# HID.net
KiCad netlist of a schematic drawn in Altium Designer
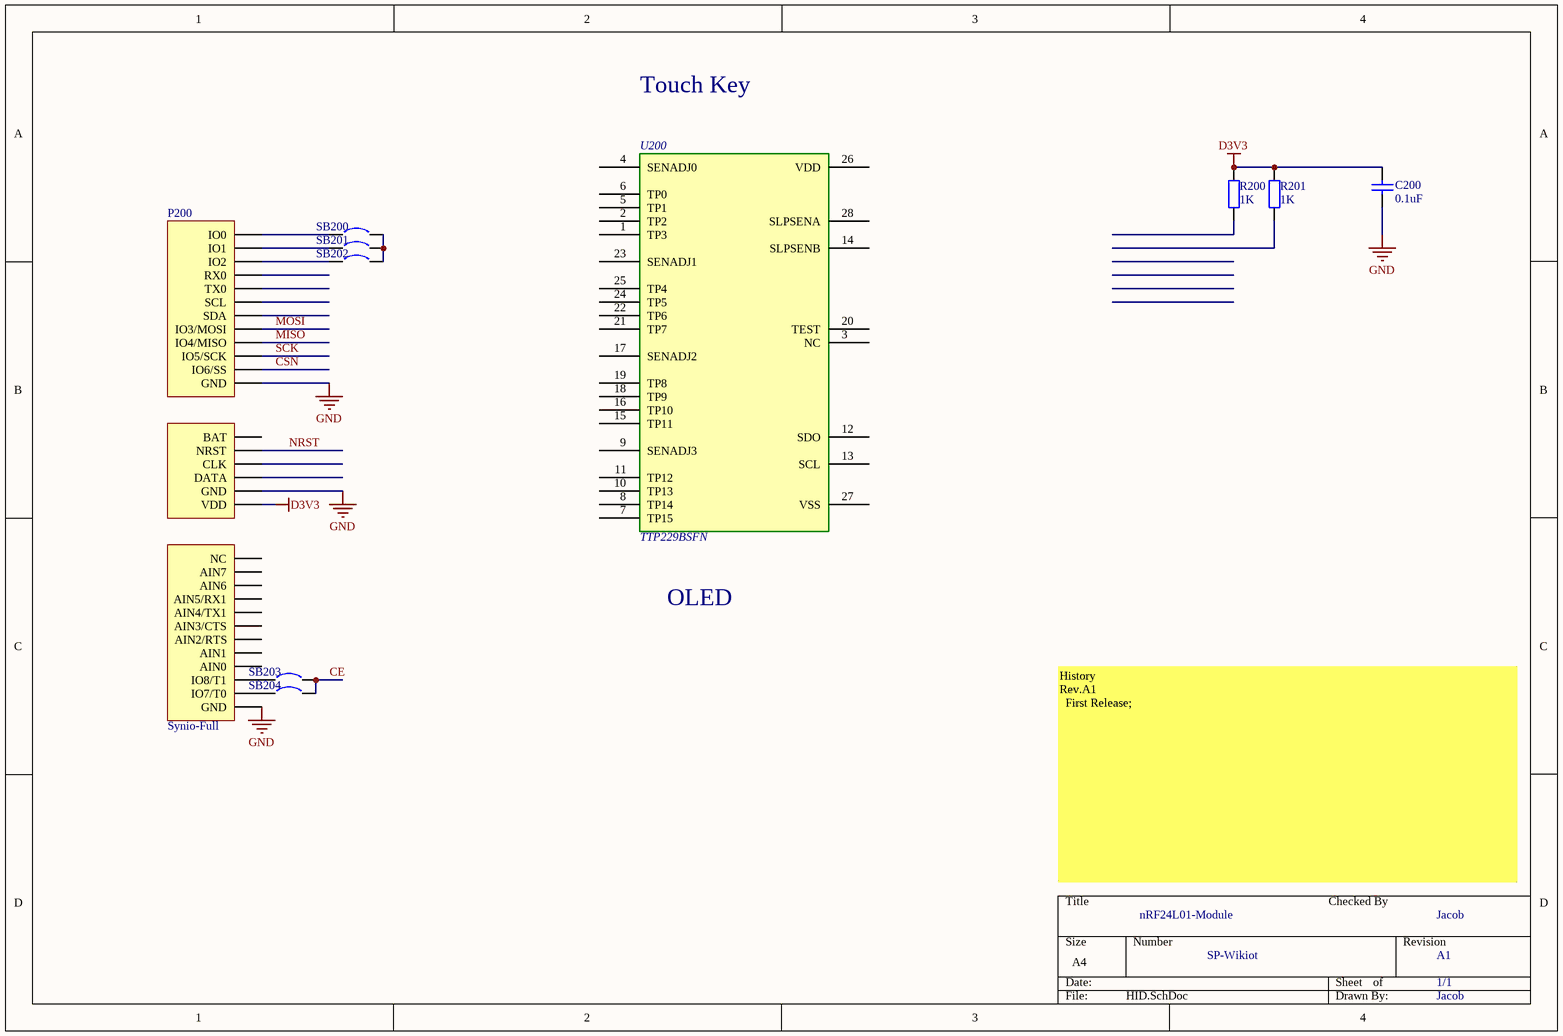
[diagram p0: HID.SchDoc]

(export (version "E")
  (design (tool "Eeschema 10.0.6"))
  (components
    (comp (ref "C200")
      (value "0.1uF")
      (footprint "C0603L")
      (description "Capacitor")
      (libsource (lib "Misc") (part "Cap"))
    )
    (comp (ref "P200")
      (value "Synio-Full")
      (footprint "Synio-Full")
      (description "Synio-Full Header")
      (libsource (lib "Connector") (part "Synio-Full"))
    )
    (comp (ref "R200")
      (value "1K")
      (footprint "R0603")
      (description "Resistor")
      (fields (field (name "PUBLISHER") "Altium Limited"))
      (libsource (lib "Misc") (part "Res"))
    )
    (comp (ref "R201")
      (value "1K")
      (footprint "R0603")
      (description "Resistor")
      (fields (field (name "PUBLISHER") "Altium Limited"))
      (libsource (lib "Misc") (part "Res"))
    )
    (comp (ref "SB200")
      (value "Circuit Breaker")
      (footprint "JP2_SMD")
      (fields (field (name "PUBLISHER") "Altium Limited"))
      (libsource (lib "Misc") (part "Circuit Breaker"))
    )
    (comp (ref "SB201")
      (value "Circuit Breaker")
      (footprint "JP2_SMD")
      (fields (field (name "PUBLISHER") "Altium Limited"))
      (libsource (lib "Misc") (part "Circuit Breaker"))
    )
    (comp (ref "SB202")
      (value "Circuit Breaker")
      (footprint "JP2_SMD")
      (fields (field (name "PUBLISHER") "Altium Limited"))
      (libsource (lib "Misc") (part "Circuit Breaker"))
    )
    (comp (ref "SB203")
      (value "Circuit Breaker")
      (footprint "JP2_SMD")
      (fields (field (name "PUBLISHER") "Altium Limited"))
      (libsource (lib "Misc") (part "Circuit Breaker"))
    )
    (comp (ref "SB204")
      (value "Circuit Breaker")
      (footprint "JP2_SMD")
      (fields (field (name "PUBLISHER") "Altium Limited"))
      (libsource (lib "Misc") (part "Circuit Breaker"))
    )
    (comp (ref "U200")
      (value "TTP229BSFN")
      (footprint "TSSOP28")
      (description "TOUCH PAD DETECTOR IC")
      (libsource (lib "Logic") (part "TP229BSFN"))
    )
  )
  (nets
    (net (code "1") (name "/CE") (class "Default")
      (node (ref "SB203") (pin "2") (pinfunction "2_2") (pintype "passive"))
      (node (ref "SB204") (pin "2") (pinfunction "2_2") (pintype "passive"))
    )
    (net (code "2") (name "/CSN") (class "Default")
      (node (ref "P200") (pin "11") (pinfunction "IO6/SS_11") (pintype "passive"))
    )
    (net (code "3") (name "/MISO") (class "Default")
      (node (ref "P200") (pin "9") (pinfunction "IO4/MISO_9") (pintype "passive"))
    )
    (net (code "4") (name "/MOSI") (class "Default")
      (node (ref "P200") (pin "8") (pinfunction "IO3/MOSI_8") (pintype "passive"))
    )
    (net (code "5") (name "/NRST") (class "Default")
      (node (ref "P200") (pin "14") (pinfunction "NRST_14") (pintype "passive"))
    )
    (net (code "6") (name "/SCK") (class "Default")
      (node (ref "P200") (pin "10") (pinfunction "IO5/SCK_10") (pintype "passive"))
    )
    (net (code "7") (name "D3V3") (class "Default")
      (node (ref "C200") (pin "1") (pinfunction "1_1") (pintype "passive"))
      (node (ref "P200") (pin "18") (pinfunction "VDD_18") (pintype "passive"))
      (node (ref "R200") (pin "1") (pinfunction "1_1") (pintype "passive"))
      (node (ref "R201") (pin "1") (pinfunction "1_1") (pintype "passive"))
    )
    (net (code "8") (name "GND") (class "Default")
      (node (ref "C200") (pin "2") (pinfunction "2_2") (pintype "passive"))
      (node (ref "P200") (pin "12") (pinfunction "GND_12") (pintype "passive"))
      (node (ref "P200") (pin "17") (pinfunction "GND_17") (pintype "passive"))
      (node (ref "P200") (pin "19") (pinfunction "GND_19") (pintype "passive"))
    )
    (net (code "9") (name "Net-(P200-IO0)") (class "Default")
      (node (ref "P200") (pin "1") (pinfunction "IO0_1") (pintype "passive"))
      (node (ref "SB200") (pin "1") (pinfunction "1_1") (pintype "passive"))
    )
    (net (code "10") (name "Net-(P200-IO1)") (class "Default")
      (node (ref "P200") (pin "2") (pinfunction "IO1_2") (pintype "passive"))
      (node (ref "SB201") (pin "1") (pinfunction "1_1") (pintype "passive"))
    )
    (net (code "11") (name "Net-(P200-IO2)") (class "Default")
      (node (ref "P200") (pin "3") (pinfunction "IO2_3") (pintype "passive"))
      (node (ref "SB202") (pin "1") (pinfunction "1_1") (pintype "passive"))
    )
    (net (code "12") (name "Net-(P200-IO7{slash}T0)") (class "Default")
      (node (ref "P200") (pin "20") (pinfunction "IO7/T0_20") (pintype "passive"))
      (node (ref "SB204") (pin "1") (pinfunction "1_1") (pintype "passive"))
    )
    (net (code "13") (name "Net-(P200-IO8{slash}T1)") (class "Default")
      (node (ref "P200") (pin "21") (pinfunction "IO8/T1_21") (pintype "passive"))
      (node (ref "SB203") (pin "1") (pinfunction "1_1") (pintype "passive"))
    )
    (net (code "14") (name "Net-(SB200-Pad2)") (class "Default")
      (node (ref "SB200") (pin "2") (pinfunction "2_2") (pintype "passive"))
      (node (ref "SB201") (pin "2") (pinfunction "2_2") (pintype "passive"))
      (node (ref "SB202") (pin "2") (pinfunction "2_2") (pintype "passive"))
    )
    (net (code "15") (name "unconnected-(P200-AIN0-Pad22)") (class "Default")
      (node (ref "P200") (pin "22") (pinfunction "AIN0_22") (pintype "passive"))
    )
    (net (code "16") (name "unconnected-(P200-AIN1-Pad23)") (class "Default")
      (node (ref "P200") (pin "23") (pinfunction "AIN1_23") (pintype "passive"))
    )
    (net (code "17") (name "unconnected-(P200-AIN2{slash}RTS-Pad24)") (class "Default")
      (node (ref "P200") (pin "24") (pinfunction "AIN2/RTS_24") (pintype "passive"))
    )
    (net (code "18") (name "unconnected-(P200-AIN3{slash}CTS-Pad25)") (class "Default")
      (node (ref "P200") (pin "25") (pinfunction "AIN3/CTS_25") (pintype "passive"))
    )
    (net (code "19") (name "unconnected-(P200-AIN4{slash}TX1-Pad26)") (class "Default")
      (node (ref "P200") (pin "26") (pinfunction "AIN4/TX1_26") (pintype "passive"))
    )
    (net (code "20") (name "unconnected-(P200-AIN5{slash}RX1-Pad27)") (class "Default")
      (node (ref "P200") (pin "27") (pinfunction "AIN5/RX1_27") (pintype "passive"))
    )
    (net (code "21") (name "unconnected-(P200-AIN6-Pad28)") (class "Default")
      (node (ref "P200") (pin "28") (pinfunction "AIN6_28") (pintype "passive"))
    )
    (net (code "22") (name "unconnected-(P200-AIN7-Pad29)") (class "Default")
      (node (ref "P200") (pin "29") (pinfunction "AIN7_29") (pintype "passive"))
    )
    (net (code "23") (name "unconnected-(P200-BAT-Pad13)") (class "Default")
      (node (ref "P200") (pin "13") (pinfunction "BAT_13") (pintype "passive"))
    )
    (net (code "24") (name "unconnected-(P200-CLK-Pad15)") (class "Default")
      (node (ref "P200") (pin "15") (pinfunction "CLK_15") (pintype "passive"))
    )
    (net (code "25") (name "unconnected-(P200-DATA-Pad16)") (class "Default")
      (node (ref "P200") (pin "16") (pinfunction "DATA_16") (pintype "passive"))
    )
    (net (code "26") (name "unconnected-(P200-NC-Pad30)") (class "Default")
      (node (ref "P200") (pin "30") (pinfunction "NC_30") (pintype "passive"))
    )
    (net (code "27") (name "unconnected-(P200-RX0-Pad4)") (class "Default")
      (node (ref "P200") (pin "4") (pinfunction "RX0_4") (pintype "passive"))
    )
    (net (code "28") (name "unconnected-(P200-SCL-Pad6)") (class "Default")
      (node (ref "P200") (pin "6") (pinfunction "SCL_6") (pintype "passive"))
    )
    (net (code "29") (name "unconnected-(P200-SDA-Pad7)") (class "Default")
      (node (ref "P200") (pin "7") (pinfunction "SDA_7") (pintype "passive"))
    )
    (net (code "30") (name "unconnected-(P200-TX0-Pad5)") (class "Default")
      (node (ref "P200") (pin "5") (pinfunction "TX0_5") (pintype "passive"))
    )
    (net (code "31") (name "unconnected-(R200-Pad2)") (class "Default")
      (node (ref "R200") (pin "2") (pinfunction "2_2") (pintype "passive"))
    )
    (net (code "32") (name "unconnected-(R201-Pad2)") (class "Default")
      (node (ref "R201") (pin "2") (pinfunction "2_2") (pintype "passive"))
    )
    (net (code "33") (name "unconnected-(U200-NC-Pad3)") (class "Default")
      (node (ref "U200") (pin "3") (pinfunction "NC_3") (pintype "passive"))
    )
    (net (code "34") (name "unconnected-(U200-SCL-Pad13)") (class "Default")
      (node (ref "U200") (pin "13") (pinfunction "SCL_13") (pintype "passive"))
    )
    (net (code "35") (name "unconnected-(U200-SDO-Pad12)") (class "Default")
      (node (ref "U200") (pin "12") (pinfunction "SDO_12") (pintype "passive"))
    )
    (net (code "36") (name "unconnected-(U200-SENADJ0-Pad4)") (class "Default")
      (node (ref "U200") (pin "4") (pinfunction "SENADJ0_4") (pintype "passive"))
    )
    (net (code "37") (name "unconnected-(U200-SENADJ1-Pad23)") (class "Default")
      (node (ref "U200") (pin "23") (pinfunction "SENADJ1_23") (pintype "passive"))
    )
    (net (code "38") (name "unconnected-(U200-SENADJ2-Pad17)") (class "Default")
      (node (ref "U200") (pin "17") (pinfunction "SENADJ2_17") (pintype "passive"))
    )
    (net (code "39") (name "unconnected-(U200-SENADJ3-Pad9)") (class "Default")
      (node (ref "U200") (pin "9") (pinfunction "SENADJ3_9") (pintype "passive"))
    )
    (net (code "40") (name "unconnected-(U200-SLPSENA-Pad28)") (class "Default")
      (node (ref "U200") (pin "28") (pinfunction "SLPSENA_28") (pintype "passive"))
    )
    (net (code "41") (name "unconnected-(U200-SLPSENB-Pad14)") (class "Default")
      (node (ref "U200") (pin "14") (pinfunction "SLPSENB_14") (pintype "passive"))
    )
    (net (code "42") (name "unconnected-(U200-TEST-Pad20)") (class "Default")
      (node (ref "U200") (pin "20") (pinfunction "TEST_20") (pintype "passive"))
    )
    (net (code "43") (name "unconnected-(U200-TP0-Pad6)") (class "Default")
      (node (ref "U200") (pin "6") (pinfunction "TP0_6") (pintype "passive"))
    )
    (net (code "44") (name "unconnected-(U200-TP1-Pad5)") (class "Default")
      (node (ref "U200") (pin "5") (pinfunction "TP1_5") (pintype "passive"))
    )
    (net (code "45") (name "unconnected-(U200-TP2-Pad2)") (class "Default")
      (node (ref "U200") (pin "2") (pinfunction "TP2_2") (pintype "passive"))
    )
    (net (code "46") (name "unconnected-(U200-TP3-Pad1)") (class "Default")
      (node (ref "U200") (pin "1") (pinfunction "TP3_1") (pintype "passive"))
    )
    (net (code "47") (name "unconnected-(U200-TP4-Pad25)") (class "Default")
      (node (ref "U200") (pin "25") (pinfunction "TP4_25") (pintype "passive"))
    )
    (net (code "48") (name "unconnected-(U200-TP5-Pad24)") (class "Default")
      (node (ref "U200") (pin "24") (pinfunction "TP5_24") (pintype "passive"))
    )
    (net (code "49") (name "unconnected-(U200-TP6-Pad22)") (class "Default")
      (node (ref "U200") (pin "22") (pinfunction "TP6_22") (pintype "passive"))
    )
    (net (code "50") (name "unconnected-(U200-TP7-Pad21)") (class "Default")
      (node (ref "U200") (pin "21") (pinfunction "TP7_21") (pintype "passive"))
    )
    (net (code "51") (name "unconnected-(U200-TP8-Pad19)") (class "Default")
      (node (ref "U200") (pin "19") (pinfunction "TP8_19") (pintype "passive"))
    )
    (net (code "52") (name "unconnected-(U200-TP9-Pad18)") (class "Default")
      (node (ref "U200") (pin "18") (pinfunction "TP9_18") (pintype "passive"))
    )
    (net (code "53") (name "unconnected-(U200-TP10-Pad16)") (class "Default")
      (node (ref "U200") (pin "16") (pinfunction "TP10_16") (pintype "passive"))
    )
    (net (code "54") (name "unconnected-(U200-TP11-Pad15)") (class "Default")
      (node (ref "U200") (pin "15") (pinfunction "TP11_15") (pintype "passive"))
    )
    (net (code "55") (name "unconnected-(U200-TP12-Pad11)") (class "Default")
      (node (ref "U200") (pin "11") (pinfunction "TP12_11") (pintype "passive"))
    )
    (net (code "56") (name "unconnected-(U200-TP13-Pad10)") (class "Default")
      (node (ref "U200") (pin "10") (pinfunction "TP13_10") (pintype "passive"))
    )
    (net (code "57") (name "unconnected-(U200-TP14-Pad8)") (class "Default")
      (node (ref "U200") (pin "8") (pinfunction "TP14_8") (pintype "passive"))
    )
    (net (code "58") (name "unconnected-(U200-TP15-Pad7)") (class "Default")
      (node (ref "U200") (pin "7") (pinfunction "TP15_7") (pintype "passive"))
    )
    (net (code "59") (name "unconnected-(U200-VDD-Pad26)") (class "Default")
      (node (ref "U200") (pin "26") (pinfunction "VDD_26") (pintype "passive"))
    )
    (net (code "60") (name "unconnected-(U200-VSS-Pad27)") (class "Default")
      (node (ref "U200") (pin "27") (pinfunction "VSS_27") (pintype "passive"))
    )
  )
)
